# Power.net
KiCad netlist of a schematic drawn in Altium Designer
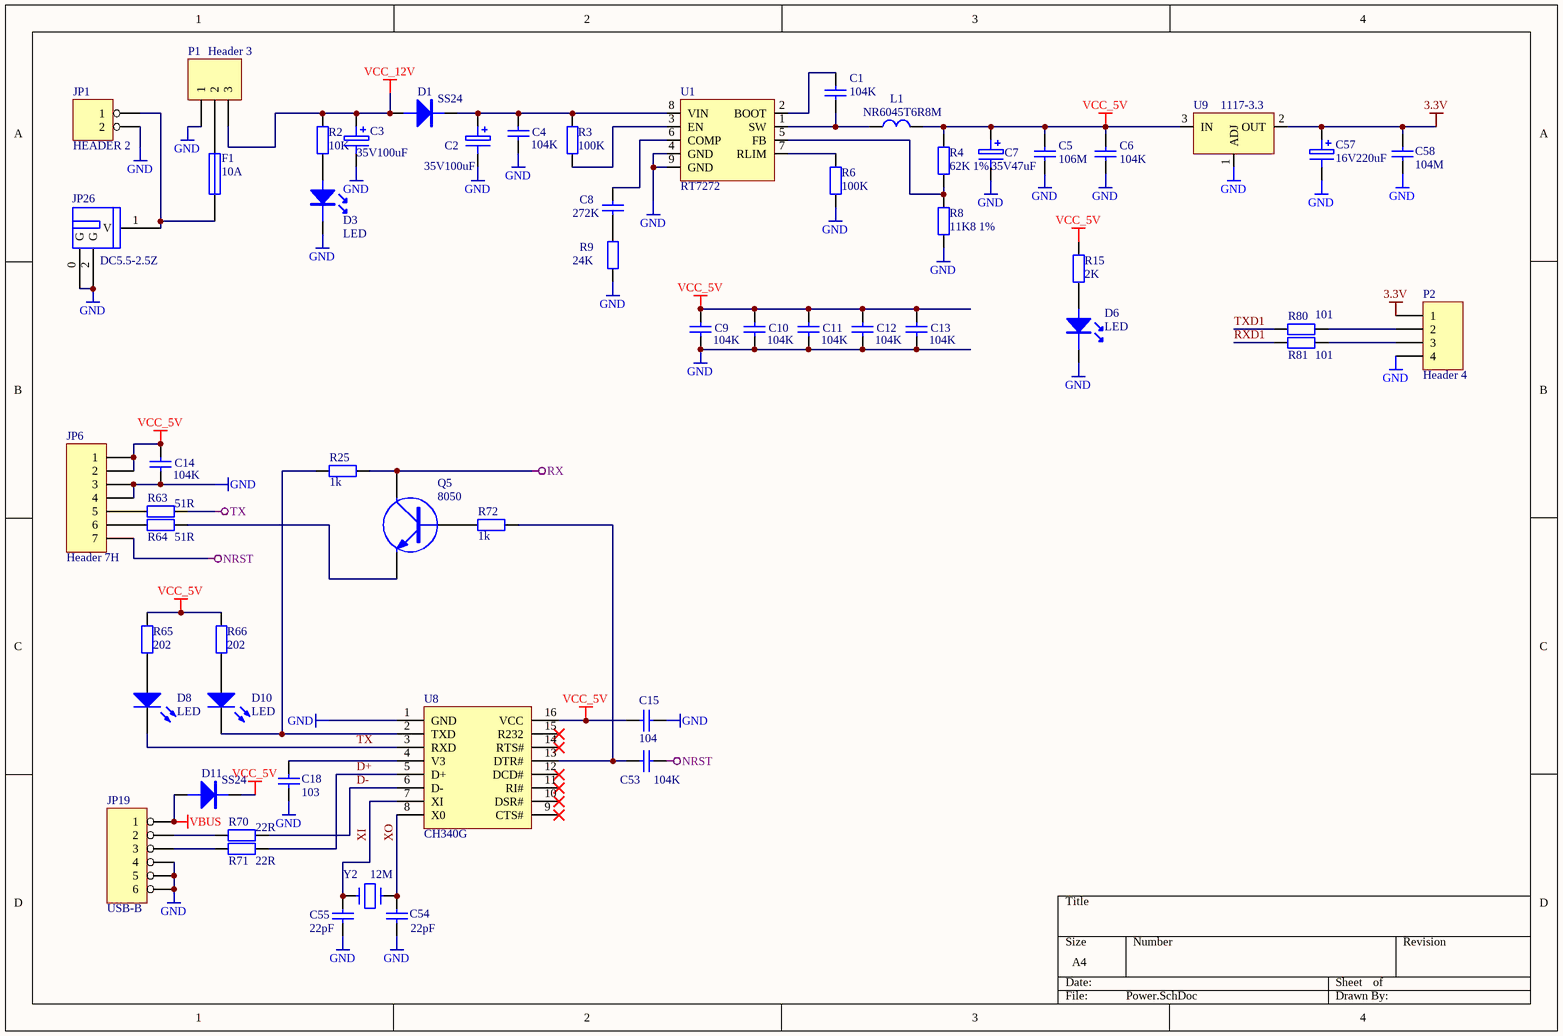
[diagram p0: Power.SchDoc]

(export (version "E")
  (design (tool "Eeschema 10.0.6"))
  (components
    (comp (ref "C1")
      (value "104K")
      (footprint "0805(CS)")
      (description "Capacitor")
      (fields (field (name "PUBLISHER") "Altium Limited"))
      (libsource (lib "Miscellaneous Devices") (part "Cap"))
    )
    (comp (ref "C2")
      (value "35V100uF")
      (footprint "F6")
      (description "Electrolytic Capacitor")
      (libsource (lib "Miscellaneous Devicespp1") (part "ELECTRO1"))
    )
    (comp (ref "C3")
      (value "35V100uF")
      (footprint "F6")
      (description "Electrolytic Capacitor")
      (libsource (lib "Miscellaneous Devicespp1") (part "ELECTRO1"))
    )
    (comp (ref "C4")
      (value "104K")
      (footprint "0805(C)")
      (description "Capacitor")
      (fields (field (name "PUBLISHER") "Altium Limited"))
      (libsource (lib "Miscellaneous Devices") (part "Cap"))
    )
    (comp (ref "C5")
      (value "106M")
      (footprint "0603(C)")
      (description "Capacitor")
      (fields (field (name "PUBLISHER") "Altium Limited"))
      (libsource (lib "Miscellaneous Devices") (part "Cap"))
    )
    (comp (ref "C6")
      (value "104K")
      (footprint "0805(CS)")
      (description "Capacitor")
      (fields (field (name "PUBLISHER") "Altium Limited"))
      (libsource (lib "Miscellaneous Devices") (part "Cap"))
    )
    (comp (ref "C7")
      (value "35V47uF")
      (footprint "F6")
      (description "Electrolytic Capacitor")
      (libsource (lib "U_PP SCH") (part "ELECTRO1"))
    )
    (comp (ref "C8")
      (value "272K")
      (footprint "0603(C)")
      (description "Capacitor")
      (fields (field (name "PUBLISHER") "Altium Limited"))
      (libsource (lib "Miscellaneous Devices") (part "Cap"))
    )
    (comp (ref "C9")
      (value "104K")
      (footprint "0805(CS)")
      (description "Capacitor")
      (fields (field (name "PUBLISHER") "Altium Limited"))
      (libsource (lib "Miscellaneous Devices") (part "Cap"))
    )
    (comp (ref "C10")
      (value "104K")
      (footprint "0805(CS)")
      (description "Capacitor")
      (fields (field (name "PUBLISHER") "Altium Limited"))
      (libsource (lib "Miscellaneous Devices") (part "Cap"))
    )
    (comp (ref "C11")
      (value "104K")
      (footprint "0805(CS)")
      (description "Capacitor")
      (fields (field (name "PUBLISHER") "Altium Limited"))
      (libsource (lib "Miscellaneous Devices") (part "Cap"))
    )
    (comp (ref "C12")
      (value "104K")
      (footprint "0805(CS)")
      (description "Capacitor")
      (fields (field (name "PUBLISHER") "Altium Limited"))
      (libsource (lib "Miscellaneous Devices") (part "Cap"))
    )
    (comp (ref "C13")
      (value "104K")
      (footprint "0805(CS)")
      (description "Capacitor")
      (fields (field (name "PUBLISHER") "Altium Limited"))
      (libsource (lib "Miscellaneous Devices") (part "Cap"))
    )
    (comp (ref "C14")
      (value "104K")
      (footprint "0805(CS)")
      (description "Capacitor")
      (fields (field (name "PUBLISHER") "Altium Limited"))
      (libsource (lib "Miscellaneous Devices") (part "Cap"))
    )
    (comp (ref "C15")
      (value "104")
      (footprint "0805(CS)")
      (description "Capacitor")
      (fields (field (name "PUBLISHER") "Altium Limited"))
      (libsource (lib "Miscellaneous Devices") (part "Cap"))
    )
    (comp (ref "C18")
      (value "103")
      (footprint "0603(C)")
      (description "Capacitor")
      (fields (field (name "PUBLISHER") "Altium Limited"))
      (libsource (lib "Miscellaneous Devices") (part "Cap"))
    )
    (comp (ref "C53")
      (value "104K")
      (footprint "0805(CS)")
      (description "Capacitor")
      (fields (field (name "PUBLISHER") "Altium Limited"))
      (libsource (lib "Miscellaneous Devices") (part "Cap"))
    )
    (comp (ref "C54")
      (value "22pF")
      (footprint "0603(C)")
      (description "Capacitor")
      (fields (field (name "PUBLISHER") "Altium Limited"))
      (libsource (lib "Miscellaneous Devices") (part "Cap"))
    )
    (comp (ref "C55")
      (value "22pF")
      (footprint "0603(C)")
      (description "Capacitor")
      (fields (field (name "PUBLISHER") "Altium Limited"))
      (libsource (lib "Miscellaneous Devices") (part "Cap"))
    )
    (comp (ref "C57")
      (value "16V220uF")
      (footprint "F6")
      (description "Electrolytic Capacitor")
      (libsource (lib "Miscellaneous Devicespp1") (part "ELECTRO1"))
    )
    (comp (ref "C58")
      (value "104M")
      (footprint "0603(C)")
      (description "Capacitor")
      (fields (field (name "PUBLISHER") "Altium Limited"))
      (libsource (lib "Miscellaneous Devices") (part "Cap"))
    )
    (comp (ref "D1")
      (value "SS24")
      (footprint "SMA")
      (description "Diode")
      (libsource (lib "U_PP SCH") (part "DIODE"))
    )
    (comp (ref "D3") (value "LED") (footprint "LED-SMD-0805") (libsource (lib "U_PP SCH") (part "LED")))
    (comp (ref "D6") (value "LED") (footprint "LED-SMD-0805") (libsource (lib "U_PP SCH") (part "LED")))
    (comp (ref "D8")
      (value "LED")
      (footprint "LED-SMD-0805")
      (description "Typical RED GaAs LED")
      (fields (field (name "PUBLISHER") "Altium Limited"))
      (libsource (lib "Miscellaneous Devices") (part "LED1"))
    )
    (comp (ref "D10")
      (value "LED")
      (footprint "LED-SMD-0805")
      (description "Typical RED GaAs LED")
      (fields (field (name "PUBLISHER") "Altium Limited"))
      (libsource (lib "Miscellaneous Devices") (part "LED1"))
    )
    (comp (ref "D11")
      (value "SS24")
      (footprint "SMA")
      (description "Diode")
      (libsource (lib "U_PP SCH") (part "DIODE"))
    )
    (comp (ref "F1")
      (value "10A")
      (footprint "1206(F)")
      (description "Fuse")
      (libsource (lib "U_PP SCH") (part "FUSE1"))
    )
    (comp (ref "JP1")
      (value "HEADER 2")
      (footprint "POWER JACK-2*5.0")
      (libsource (lib "U_PP SCH") (part "HEADER 2"))
    )
    (comp (ref "JP6")
      (value "Header 7H")
      (footprint "XH2.54-7P")
      (description "Header, 7-Pin, Right Angle")
      (fields (field (name "PUBLISHER") "Altium Limited"))
      (libsource (lib "Miscellaneous Connectors") (part "Header 7H"))
    )
    (comp (ref "JP19") (value "USB-B") (footprint "USBBW") (libsource (lib "U_PP SCH") (part "HEADER 6")))
    (comp (ref "JP26")
      (value "DC5.5-2.5Z")
      (footprint "DC-528")
      (libsource (lib "zbhSchLib") (part "DC5.5-2.5Z"))
    )
    (comp (ref "L1")
      (value "NR6045T6R8M")
      (footprint "COKE_6X6")
      (libsource (lib "Miscellaneous Devicespp1") (part "INDUCTOR"))
    )
    (comp (ref "P1")
      (value "Header 3")
      (footprint "POWER JACK-3*5.0")
      (description "Header, 3-Pin")
      (fields (field (name "PUBLISHER") "Altium Limited"))
      (libsource (lib "Miscellaneous Connectors") (part "Header 3"))
    )
    (comp (ref "P2")
      (value "Header 4")
      (footprint "HDR1X4")
      (description "Header, 4-Pin")
      (fields (field (name "PUBLISHER") "Altium Limited"))
      (libsource (lib "Miscellaneous Connectors") (part "Header 4"))
    )
    (comp (ref "Q5")
      (value "8050")
      (footprint "SOT23")
      (description "NPN Transistor")
      (libsource (lib "Miscellaneous Devicespp1") (part "NPN"))
    )
    (comp (ref "R2")
      (value "10K")
      (footprint "0603(R)")
      (description "Resistor")
      (fields (field (name "PUBLISHER") "Altium Limited"))
      (libsource (lib "") (part "Res2_2"))
    )
    (comp (ref "R3")
      (value "100K")
      (footprint "0603(R)")
      (description "Resistor")
      (fields (field (name "PUBLISHER") "Altium Limited"))
      (libsource (lib "") (part "Res2_2"))
    )
    (comp (ref "R4")
      (value "62K 1%")
      (footprint "0603(R)")
      (description "Resistor")
      (fields (field (name "PUBLISHER") "Altium Limited"))
      (libsource (lib "") (part "Res2_2"))
    )
    (comp (ref "R6")
      (value "100K")
      (footprint "0603(R)")
      (description "Resistor")
      (fields (field (name "PUBLISHER") "Altium Limited"))
      (libsource (lib "") (part "Res2_2"))
    )
    (comp (ref "R8")
      (value "11K8 1%")
      (footprint "0603(R)")
      (description "Resistor")
      (fields (field (name "PUBLISHER") "Altium Limited"))
      (libsource (lib "") (part "Res2_2"))
    )
    (comp (ref "R9")
      (value "24K")
      (footprint "0603(R)")
      (description "Resistor")
      (fields (field (name "PUBLISHER") "Altium Limited"))
      (libsource (lib "") (part "Res2_2"))
    )
    (comp (ref "R15")
      (value "2K")
      (footprint "0603(R)")
      (description "Resistor")
      (fields (field (name "PUBLISHER") "Altium Limited"))
      (libsource (lib "") (part "Res2_2"))
    )
    (comp (ref "R25")
      (value "1k")
      (footprint "0603(R)")
      (description "Resistor")
      (fields (field (name "PUBLISHER") "Altium Limited"))
      (libsource (lib "") (part "Res2_1"))
    )
    (comp (ref "R63")
      (value "51R")
      (footprint "0603(R)")
      (description "Resistor")
      (fields (field (name "PUBLISHER") "Altium Limited"))
      (libsource (lib "Miscellaneous Devices") (part "Res2"))
    )
    (comp (ref "R64")
      (value "51R")
      (footprint "0603(R)")
      (description "Resistor")
      (fields (field (name "PUBLISHER") "Altium Limited"))
      (libsource (lib "Miscellaneous Devices") (part "Res2"))
    )
    (comp (ref "R65")
      (value "202")
      (footprint "0603(R)")
      (description "Resistor")
      (fields (field (name "PUBLISHER") "Altium Limited"))
      (libsource (lib "") (part "Res2_3"))
    )
    (comp (ref "R66")
      (value "202")
      (footprint "0603(R)")
      (description "Resistor")
      (fields (field (name "PUBLISHER") "Altium Limited"))
      (libsource (lib "") (part "Res2_3"))
    )
    (comp (ref "R70")
      (value "22R")
      (footprint "0603(R)")
      (description "Resistor")
      (fields (field (name "PUBLISHER") "Altium Limited"))
      (libsource (lib "Miscellaneous Devices") (part "Res2"))
    )
    (comp (ref "R71")
      (value "22R")
      (footprint "0603(R)")
      (description "Resistor")
      (fields (field (name "PUBLISHER") "Altium Limited"))
      (libsource (lib "Miscellaneous Devices") (part "Res2"))
    )
    (comp (ref "R72")
      (value "1k")
      (footprint "0603(R)")
      (description "Resistor")
      (fields (field (name "PUBLISHER") "Altium Limited"))
      (libsource (lib "") (part "Res2_1"))
    )
    (comp (ref "R80")
      (value "101")
      (footprint "0603(R)")
      (description "Resistor")
      (fields (field (name "PUBLISHER") "Altium Limited"))
      (libsource (lib "Miscellaneous Devices") (part "Res2"))
    )
    (comp (ref "R81")
      (value "101")
      (footprint "0603(R)")
      (description "Resistor")
      (fields (field (name "PUBLISHER") "Altium Limited"))
      (libsource (lib "Miscellaneous Devices") (part "Res2"))
    )
    (comp (ref "U1") (value "RT7272") (footprint "SO8-EP") (libsource (lib "U_PP SCH") (part "RT7272")))
    (comp (ref "U8")
      (value "CH340G")
      (footprint "SO-16")
      (libsource (lib "Miscellaneous Devicespp1") (part "CH340G"))
    )
    (comp (ref "U9")
      (value "1117-3.3")
      (footprint "SOT223-1117")
      (libsource (lib "Miscellaneous Devicespp1") (part "1117"))
    )
    (comp (ref "Y2")
      (value "12M")
      (footprint "CRYS-SMD-5032-2P")
      (description "Crystal")
      (libsource (lib "Miscellaneous Devicespp1") (part "CRYSTAL"))
    )
  )
  (nets
    (net (code "1") (name "/D+") (class "Default")
      (node (ref "R71") (pin "2") (pinfunction "2_2") (pintype "passive"))
      (node (ref "U8") (pin "5") (pinfunction "D+_5") (pintype "passive"))
    )
    (net (code "2") (name "/D-") (class "Default")
      (node (ref "R70") (pin "2") (pinfunction "2_2") (pintype "passive"))
      (node (ref "U8") (pin "6") (pinfunction "D-_6") (pintype "passive"))
    )
    (net (code "3") (name "/RXD1") (class "Default")
      (node (ref "R81") (pin "1") (pinfunction "1_1") (pintype "passive"))
    )
    (net (code "4") (name "/TXD1") (class "Default")
      (node (ref "R80") (pin "1") (pinfunction "1_1") (pintype "passive"))
    )
    (net (code "5") (name "/XI") (class "Default")
      (node (ref "C55") (pin "1") (pinfunction "1_1") (pintype "passive"))
      (node (ref "U8") (pin "7") (pinfunction "XI_7") (pintype "passive"))
      (node (ref "Y2") (pin "1") (pinfunction "1_1") (pintype "passive"))
    )
    (net (code "6") (name "/XO") (class "Default")
      (node (ref "C54") (pin "1") (pinfunction "1_1") (pintype "passive"))
      (node (ref "U8") (pin "8") (pinfunction "X0_8") (pintype "passive"))
      (node (ref "Y2") (pin "2") (pinfunction "2_2") (pintype "passive"))
    )
    (net (code "7") (name "3.3V") (class "Default")
      (node (ref "C57") (pin "1") (pinfunction "1_1") (pintype "passive"))
      (node (ref "C58") (pin "2") (pinfunction "2_2") (pintype "passive"))
      (node (ref "P2") (pin "1") (pinfunction "1_1") (pintype "passive"))
      (node (ref "U9") (pin "2") (pinfunction "OUT_2") (pintype "passive"))
    )
    (net (code "8") (name "GND") (class "Default")
      (node (ref "C10") (pin "1") (pinfunction "1_1") (pintype "passive"))
      (node (ref "C11") (pin "1") (pinfunction "1_1") (pintype "passive"))
      (node (ref "C12") (pin "1") (pinfunction "1_1") (pintype "passive"))
      (node (ref "C13") (pin "1") (pinfunction "1_1") (pintype "passive"))
      (node (ref "C14") (pin "1") (pinfunction "1_1") (pintype "passive"))
      (node (ref "C15") (pin "1") (pinfunction "1_1") (pintype "passive"))
      (node (ref "C18") (pin "1") (pinfunction "1_1") (pintype "passive"))
      (node (ref "C2") (pin "2") (pinfunction "2_2") (pintype "passive"))
      (node (ref "C3") (pin "2") (pinfunction "2_2") (pintype "passive"))
      (node (ref "C4") (pin "1") (pinfunction "1_1") (pintype "passive"))
      (node (ref "C5") (pin "1") (pinfunction "1_1") (pintype "passive"))
      (node (ref "C54") (pin "2") (pinfunction "2_2") (pintype "passive"))
      (node (ref "C55") (pin "2") (pinfunction "2_2") (pintype "passive"))
      (node (ref "C57") (pin "2") (pinfunction "2_2") (pintype "passive"))
      (node (ref "C58") (pin "1") (pinfunction "1_1") (pintype "passive"))
      (node (ref "C6") (pin "1") (pinfunction "1_1") (pintype "passive"))
      (node (ref "C7") (pin "2") (pinfunction "2_2") (pintype "passive"))
      (node (ref "C9") (pin "1") (pinfunction "1_1") (pintype "passive"))
      (node (ref "D3") (pin "2") (pinfunction "2_2") (pintype "passive"))
      (node (ref "D6") (pin "2") (pinfunction "2_2") (pintype "passive"))
      (node (ref "JP1") (pin "2") (pinfunction "2_2") (pintype "passive"))
      (node (ref "JP19") (pin "4") (pinfunction "4_4") (pintype "passive"))
      (node (ref "JP19") (pin "5") (pinfunction "5_5") (pintype "passive"))
      (node (ref "JP19") (pin "6") (pinfunction "6_6") (pintype "passive"))
      (node (ref "JP26") (pin "0") (pinfunction "G_0") (pintype "passive"))
      (node (ref "JP26") (pin "2") (pinfunction "G_2") (pintype "passive"))
      (node (ref "JP6") (pin "3") (pinfunction "3_3") (pintype "passive"))
      (node (ref "JP6") (pin "4") (pinfunction "4_4") (pintype "passive"))
      (node (ref "P1") (pin "1") (pinfunction "1_1") (pintype "passive"))
      (node (ref "P2") (pin "4") (pinfunction "4_4") (pintype "passive"))
      (node (ref "R6") (pin "2") (pinfunction "2_2") (pintype "passive"))
      (node (ref "R8") (pin "2") (pinfunction "2_2") (pintype "passive"))
      (node (ref "R9") (pin "2") (pinfunction "2_2") (pintype "passive"))
      (node (ref "U1") (pin "4") (pinfunction "GND_4") (pintype "passive"))
      (node (ref "U1") (pin "9") (pinfunction "GND_9") (pintype "passive"))
      (node (ref "U8") (pin "1") (pinfunction "GND_1") (pintype "passive"))
      (node (ref "U9") (pin "1") (pinfunction "ADJ_1") (pintype "passive"))
    )
    (net (code "9") (name "NRST") (class "Default")
      (node (ref "C53") (pin "2") (pinfunction "2_2") (pintype "passive"))
      (node (ref "JP6") (pin "7") (pinfunction "7_7") (pintype "passive"))
    )
    (net (code "10") (name "Net-(C8-Pad1)") (class "Default")
      (node (ref "C8") (pin "1") (pinfunction "1_1") (pintype "passive"))
      (node (ref "R9") (pin "1") (pinfunction "1_1") (pintype "passive"))
    )
    (net (code "11") (name "Net-(D3-Pad1)") (class "Default")
      (node (ref "D3") (pin "1") (pinfunction "1_1") (pintype "passive"))
      (node (ref "R2") (pin "2") (pinfunction "2_2") (pintype "passive"))
    )
    (net (code "12") (name "Net-(D6-Pad1)") (class "Default")
      (node (ref "D6") (pin "1") (pinfunction "1_1") (pintype "passive"))
      (node (ref "R15") (pin "2") (pinfunction "2_2") (pintype "passive"))
    )
    (net (code "13") (name "Net-(D8-A)") (class "Default")
      (node (ref "D8") (pin "1") (pinfunction "A_1") (pintype "passive"))
      (node (ref "R65") (pin "1") (pinfunction "1_1") (pintype "passive"))
    )
    (net (code "14") (name "Net-(D10-A)") (class "Default")
      (node (ref "D10") (pin "1") (pinfunction "A_1") (pintype "passive"))
      (node (ref "R66") (pin "1") (pinfunction "1_1") (pintype "passive"))
    )
    (net (code "15") (name "Net-(D10-K)") (class "Default")
      (node (ref "D10") (pin "2") (pinfunction "K_2") (pintype "passive"))
      (node (ref "R25") (pin "2") (pinfunction "2_2") (pintype "passive"))
      (node (ref "U8") (pin "2") (pinfunction "TXD_2") (pintype "passive"))
    )
    (net (code "16") (name "Net-(F1-Pad1)") (class "Default")
      (node (ref "F1") (pin "1") (pinfunction "1_1") (pintype "passive"))
      (node (ref "P1") (pin "2") (pinfunction "2_2") (pintype "passive"))
    )
    (net (code "17") (name "Net-(JP6-Pad5)") (class "Default")
      (node (ref "JP6") (pin "5") (pinfunction "5_5") (pintype "passive"))
      (node (ref "R63") (pin "1") (pinfunction "1_1") (pintype "passive"))
    )
    (net (code "18") (name "Net-(JP6-Pad6)") (class "Default")
      (node (ref "JP6") (pin "6") (pinfunction "6_6") (pintype "passive"))
      (node (ref "R64") (pin "1") (pinfunction "1_1") (pintype "passive"))
    )
    (net (code "19") (name "Net-(JP19-Pad2)") (class "Default")
      (node (ref "JP19") (pin "2") (pinfunction "2_2") (pintype "passive"))
      (node (ref "R70") (pin "1") (pinfunction "1_1") (pintype "passive"))
    )
    (net (code "20") (name "Net-(JP19-Pad3)") (class "Default")
      (node (ref "JP19") (pin "3") (pinfunction "3_3") (pintype "passive"))
      (node (ref "R71") (pin "1") (pinfunction "1_1") (pintype "passive"))
    )
    (net (code "21") (name "Net-(JP26-V)") (class "Default")
      (node (ref "F1") (pin "2") (pinfunction "2_2") (pintype "passive"))
      (node (ref "JP1") (pin "1") (pinfunction "1_1") (pintype "passive"))
      (node (ref "JP26") (pin "1") (pinfunction "V_1") (pintype "passive"))
    )
    (net (code "22") (name "Net-(P2-Pad2)") (class "Default")
      (node (ref "P2") (pin "2") (pinfunction "2_2") (pintype "passive"))
      (node (ref "R80") (pin "2") (pinfunction "2_2") (pintype "passive"))
    )
    (net (code "23") (name "Net-(P2-Pad3)") (class "Default")
      (node (ref "P2") (pin "3") (pinfunction "3_3") (pintype "passive"))
      (node (ref "R81") (pin "2") (pinfunction "2_2") (pintype "passive"))
    )
    (net (code "24") (name "Net-(Q5-B)") (class "Default")
      (node (ref "Q5") (pin "1") (pinfunction "B_1") (pintype "passive"))
      (node (ref "R72") (pin "2") (pinfunction "2_2") (pintype "passive"))
    )
    (net (code "25") (name "Net-(Q5-E)") (class "Default")
      (node (ref "Q5") (pin "2") (pinfunction "E_2") (pintype "passive"))
      (node (ref "R64") (pin "2") (pinfunction "2_2") (pintype "passive"))
    )
    (net (code "26") (name "Net-(U1-BOOT)") (class "Default")
      (node (ref "C1") (pin "2") (pinfunction "2_2") (pintype "passive"))
      (node (ref "U1") (pin "2") (pinfunction "BOOT_2") (pintype "passive"))
    )
    (net (code "27") (name "Net-(U1-COMP)") (class "Default")
      (node (ref "C8") (pin "2") (pinfunction "2_2") (pintype "passive"))
      (node (ref "U1") (pin "6") (pinfunction "COMP_6") (pintype "passive"))
    )
    (net (code "28") (name "Net-(U1-EN)") (class "Default")
      (node (ref "R3") (pin "2") (pinfunction "2_2") (pintype "passive"))
      (node (ref "U1") (pin "3") (pinfunction "EN_3") (pintype "passive"))
    )
    (net (code "29") (name "Net-(U1-FB)") (class "Default")
      (node (ref "R4") (pin "2") (pinfunction "2_2") (pintype "passive"))
      (node (ref "R8") (pin "1") (pinfunction "1_1") (pintype "passive"))
      (node (ref "U1") (pin "5") (pinfunction "FB_5") (pintype "passive"))
    )
    (net (code "30") (name "Net-(U1-RLIM)") (class "Default")
      (node (ref "R6") (pin "1") (pinfunction "1_1") (pintype "passive"))
      (node (ref "U1") (pin "7") (pinfunction "RLIM_7") (pintype "passive"))
    )
    (net (code "31") (name "Net-(U1-SW)") (class "Default")
      (node (ref "C1") (pin "1") (pinfunction "1_1") (pintype "passive"))
      (node (ref "L1") (pin "1") (pinfunction "1_1") (pintype "passive"))
      (node (ref "U1") (pin "1") (pinfunction "SW_1") (pintype "passive"))
    )
    (net (code "32") (name "Net-(U1-VIN)") (class "Default")
      (node (ref "C2") (pin "1") (pinfunction "1_1") (pintype "passive"))
      (node (ref "C4") (pin "2") (pinfunction "2_2") (pintype "passive"))
      (node (ref "D1") (pin "2") (pinfunction "2_2") (pintype "passive"))
      (node (ref "R3") (pin "1") (pinfunction "1_1") (pintype "passive"))
      (node (ref "U1") (pin "8") (pinfunction "VIN_8") (pintype "passive"))
    )
    (net (code "33") (name "Net-(U8-DTR#)") (class "Default")
      (node (ref "C53") (pin "1") (pinfunction "1_1") (pintype "passive"))
      (node (ref "R72") (pin "1") (pinfunction "1_1") (pintype "passive"))
      (node (ref "U8") (pin "13") (pinfunction "DTR#_13") (pintype "passive"))
    )
    (net (code "34") (name "Net-(U8-V3)") (class "Default")
      (node (ref "C18") (pin "2") (pinfunction "2_2") (pintype "passive"))
      (node (ref "U8") (pin "4") (pinfunction "V3_4") (pintype "passive"))
    )
    (net (code "35") (name "RX") (class "Default")
      (node (ref "Q5") (pin "3") (pinfunction "C_3") (pintype "passive"))
      (node (ref "R25") (pin "1") (pinfunction "1_1") (pintype "passive"))
    )
    (net (code "36") (name "TX") (class "Default")
      (node (ref "D8") (pin "2") (pinfunction "K_2") (pintype "passive"))
      (node (ref "R63") (pin "2") (pinfunction "2_2") (pintype "passive"))
      (node (ref "U8") (pin "3") (pinfunction "RXD_3") (pintype "passive"))
    )
    (net (code "37") (name "VBUS") (class "Default")
      (node (ref "D11") (pin "1") (pinfunction "1_1") (pintype "passive"))
      (node (ref "JP19") (pin "1") (pinfunction "1_1") (pintype "passive"))
    )
    (net (code "38") (name "VCC_5V") (class "Default")
      (node (ref "C10") (pin "2") (pinfunction "2_2") (pintype "passive"))
      (node (ref "C11") (pin "2") (pinfunction "2_2") (pintype "passive"))
      (node (ref "C12") (pin "2") (pinfunction "2_2") (pintype "passive"))
      (node (ref "C13") (pin "2") (pinfunction "2_2") (pintype "passive"))
      (node (ref "C14") (pin "2") (pinfunction "2_2") (pintype "passive"))
      (node (ref "C15") (pin "2") (pinfunction "2_2") (pintype "passive"))
      (node (ref "C5") (pin "2") (pinfunction "2_2") (pintype "passive"))
      (node (ref "C6") (pin "2") (pinfunction "2_2") (pintype "passive"))
      (node (ref "C7") (pin "1") (pinfunction "1_1") (pintype "passive"))
      (node (ref "C9") (pin "2") (pinfunction "2_2") (pintype "passive"))
      (node (ref "D11") (pin "2") (pinfunction "2_2") (pintype "passive"))
      (node (ref "JP6") (pin "1") (pinfunction "1_1") (pintype "passive"))
      (node (ref "JP6") (pin "2") (pinfunction "2_2") (pintype "passive"))
      (node (ref "L1") (pin "2") (pinfunction "2_2") (pintype "passive"))
      (node (ref "R15") (pin "1") (pinfunction "1_1") (pintype "passive"))
      (node (ref "R4") (pin "1") (pinfunction "1_1") (pintype "passive"))
      (node (ref "R65") (pin "2") (pinfunction "2_2") (pintype "passive"))
      (node (ref "R66") (pin "2") (pinfunction "2_2") (pintype "passive"))
      (node (ref "U8") (pin "16") (pinfunction "VCC_16") (pintype "passive"))
      (node (ref "U9") (pin "3") (pinfunction "IN_3") (pintype "passive"))
    )
    (net (code "39") (name "VCC_12V") (class "Default")
      (node (ref "C3") (pin "1") (pinfunction "1_1") (pintype "passive"))
      (node (ref "D1") (pin "1") (pinfunction "1_1") (pintype "passive"))
      (node (ref "P1") (pin "3") (pinfunction "3_3") (pintype "passive"))
      (node (ref "R2") (pin "1") (pinfunction "1_1") (pintype "passive"))
    )
    (net (code "40") (name "unconnected-(U8-CTS#-Pad9)") (class "Default")
      (node (ref "U8") (pin "9") (pinfunction "CTS#_9") (pintype "passive+no_connect"))
    )
    (net (code "41") (name "unconnected-(U8-DCD#-Pad12)") (class "Default")
      (node (ref "U8") (pin "12") (pinfunction "DCD#_12") (pintype "passive+no_connect"))
    )
    (net (code "42") (name "unconnected-(U8-DSR#-Pad10)") (class "Default")
      (node (ref "U8") (pin "10") (pinfunction "DSR#_10") (pintype "passive+no_connect"))
    )
    (net (code "43") (name "unconnected-(U8-R232-Pad15)") (class "Default")
      (node (ref "U8") (pin "15") (pinfunction "R232_15") (pintype "passive+no_connect"))
    )
    (net (code "44") (name "unconnected-(U8-RI#-Pad11)") (class "Default")
      (node (ref "U8") (pin "11") (pinfunction "RI#_11") (pintype "passive+no_connect"))
    )
    (net (code "45") (name "unconnected-(U8-RTS#-Pad14)") (class "Default")
      (node (ref "U8") (pin "14") (pinfunction "RTS#_14") (pintype "passive+no_connect"))
    )
  )
)
